# POWER.net
KiCad netlist of a schematic drawn in Altium Designer
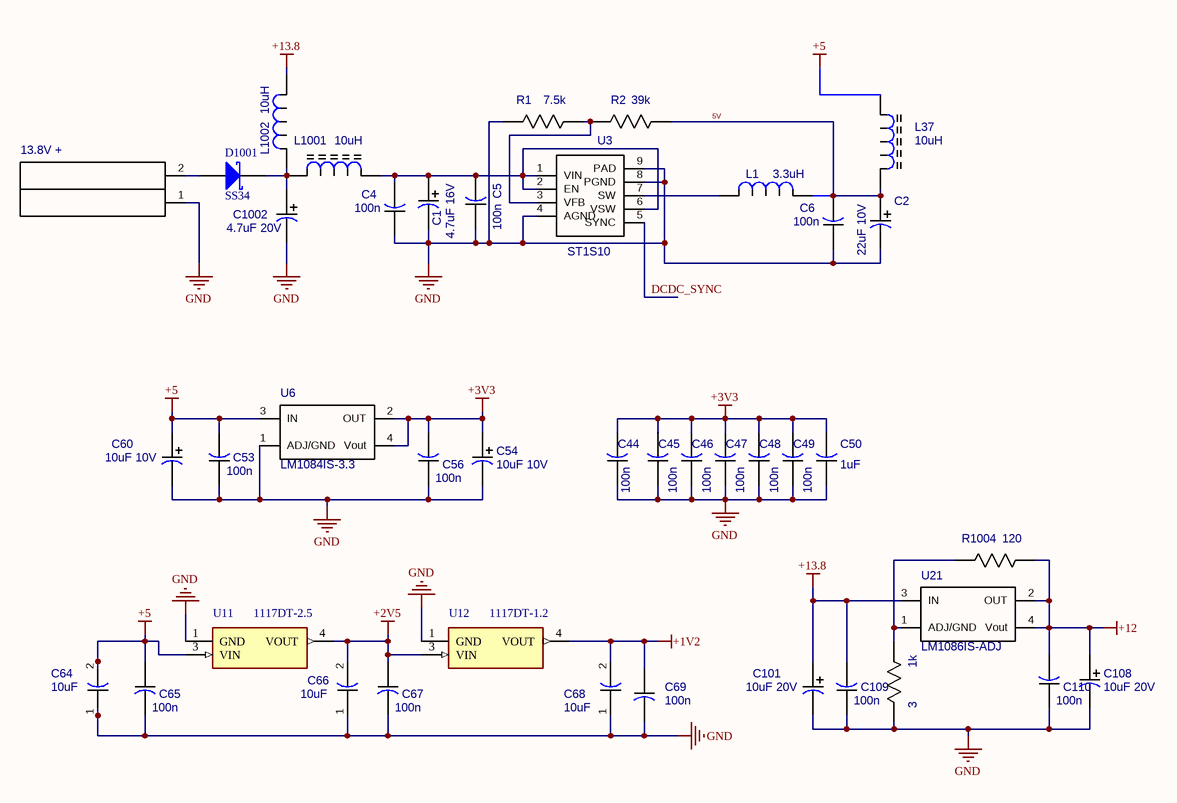
[diagram p0: POWER.SchDoc]

(export (version "E")
  (design (tool "Eeschema 10.0.6"))
  (components
    (comp (ref "3")
      (value "1k")
      (footprint "RES_0805")
      (description "RES_0805")
      (fields (field (name "Comment") "39k"))
      (libsource (lib "*") (part "RES_0805"))
    )
    (comp (ref "13.8V +") (value "JX2") (footprint "JX2") (libsource (lib "*") (part "JX2")))
    (comp (ref "C1")
      (value "4.7uF 16V")
      (footprint "SMC")
      (description "CAPAE_6.6x6.6h5.4")
      (libsource (lib "*") (part "CAPAE_6.6x6.6h5.4"))
    )
    (comp (ref "C2")
      (value "22uF 10V")
      (footprint "CAPAE_4.3x4.3h5.4")
      (description "CAPAE_4.3x4.3h5.4")
      (libsource (lib "*") (part "CAPAE_4.3x4.3h5.4"))
    )
    (comp (ref "C4")
      (value "100n")
      (footprint "CAP_0805")
      (description "CAP_0805")
      (libsource (lib "*") (part "CAP_0805"))
    )
    (comp (ref "C5")
      (value "100n")
      (footprint "CAP_0805")
      (description "CAP_0805")
      (libsource (lib "*") (part "CAP_0805"))
    )
    (comp (ref "C6")
      (value "100n")
      (footprint "CAP_0805")
      (description "CAP_0805")
      (libsource (lib "*") (part "CAP_0805"))
    )
    (comp (ref "C44")
      (value "100n")
      (footprint "CAP_0805")
      (description "CAP_0805")
      (libsource (lib "*") (part "CAP_0805"))
    )
    (comp (ref "C45")
      (value "100n")
      (footprint "CAP_0805")
      (description "CAP_0805")
      (libsource (lib "*") (part "CAP_0805"))
    )
    (comp (ref "C46")
      (value "100n")
      (footprint "CAP_0805")
      (description "CAP_0805")
      (libsource (lib "*") (part "CAP_0805"))
    )
    (comp (ref "C47")
      (value "100n")
      (footprint "CAP_0805")
      (description "CAP_0805")
      (libsource (lib "*") (part "CAP_0805"))
    )
    (comp (ref "C48")
      (value "100n")
      (footprint "CAP_0805")
      (description "CAP_0805")
      (libsource (lib "*") (part "CAP_0805"))
    )
    (comp (ref "C49")
      (value "100n")
      (footprint "CAP_0805")
      (description "CAP_0805")
      (libsource (lib "*") (part "CAP_0805"))
    )
    (comp (ref "C50")
      (value "1uF")
      (footprint "CAP_0805")
      (description "CAP_0805")
      (fields (field (name "Comment") "10uF"))
      (libsource (lib "*") (part "CAP_0805"))
    )
    (comp (ref "C53")
      (value "100n")
      (footprint "CAP_0805")
      (description "CAP_0805")
      (libsource (lib "*") (part "CAP_0805"))
    )
    (comp (ref "C54")
      (value "10uF 10V")
      (footprint "CAPAE_4.3x4.3h5.4")
      (description "CAPAE_4.3x4.3h5.4")
      (libsource (lib "*") (part "CAPAE_4.3x4.3h5.4"))
    )
    (comp (ref "C56")
      (value "100n")
      (footprint "CAP_0805")
      (description "CAP_0805")
      (libsource (lib "*") (part "CAP_0805"))
    )
    (comp (ref "C60")
      (value "10uF 10V")
      (footprint "CAPAE_4.3x4.3h5.4")
      (description "CAPAE_4.3x4.3h5.4")
      (libsource (lib "*") (part "CAPAE_4.3x4.3h5.4"))
    )
    (comp (ref "C64")
      (value "10uF")
      (footprint "CAP_0805")
      (description "CAP_0805")
      (libsource (lib "MOTHERBOARD") (part "CAP_0805"))
    )
    (comp (ref "C65")
      (value "100n")
      (footprint "CAP_0805")
      (description "CAP_0805")
      (libsource (lib "*") (part "CAP_0805"))
    )
    (comp (ref "C66")
      (value "10uF")
      (footprint "CAP_0805")
      (description "CAP_0805")
      (libsource (lib "MOTHERBOARD") (part "CAP_0805"))
    )
    (comp (ref "C67")
      (value "100n")
      (footprint "CAP_0805")
      (description "CAP_0805")
      (libsource (lib "*") (part "CAP_0805"))
    )
    (comp (ref "C68")
      (value "10uF")
      (footprint "CAP_0805")
      (description "CAP_0805")
      (libsource (lib "MOTHERBOARD") (part "CAP_0805"))
    )
    (comp (ref "C69")
      (value "100n")
      (footprint "CAP_0805")
      (description "CAP_0805")
      (libsource (lib "*") (part "CAP_0805"))
    )
    (comp (ref "C101")
      (value "10uF 20V")
      (footprint "CAPAE_4.3x4.3h5.4")
      (description "CAPAE_4.3x4.3h5.4")
      (libsource (lib "*") (part "CAPAE_4.3x4.3h5.4"))
    )
    (comp (ref "C108")
      (value "10uF 20V")
      (footprint "CAPAE_4.3x4.3h5.4")
      (description "CAPAE_4.3x4.3h5.4")
      (libsource (lib "*") (part "CAPAE_4.3x4.3h5.4"))
    )
    (comp (ref "C109")
      (value "100n")
      (footprint "CAP_0805")
      (description "CAP_0805")
      (libsource (lib "*") (part "CAP_0805"))
    )
    (comp (ref "C110")
      (value "100n")
      (footprint "CAP_0805")
      (description "CAP_0805")
      (libsource (lib "*") (part "CAP_0805"))
    )
    (comp (ref "C1002")
      (value "4.7uF 20V")
      (footprint "CAPAE_4.3x4.3h5.4")
      (description "CAPAE_4.3x4.3h5.4")
      (fields (field (name "Comment") "10uF 10V"))
      (libsource (lib "*") (part "CAPAE_4.3x4.3h5.4"))
    )
    (comp (ref "D1001")
      (value "SS34")
      (footprint "SMB")
      (description "Schottky Diode")
      (fields (field (name "PUBLISHER") "Altium Limited"))
      (libsource (lib "Miscellaneous Devices") (part "D Schottky"))
    )
    (comp (ref "L1")
      (value "3.3uH")
      (footprint "IND_1812")
      (description "IND_1812")
      (libsource (lib "*") (part "IND_1812"))
    )
    (comp (ref "L37")
      (value "10uH")
      (footprint "IND_7x7")
      (description "Inductor")
      (libsource (lib "MOTHERBOARD_1") (part "IND_FERRITE_CORE"))
    )
    (comp (ref "L1001")
      (value "10uH")
      (footprint "IND_7x7")
      (description "Inductor")
      (libsource (lib "MOTHERBOARD_1") (part "IND_FERRITE_CORE"))
    )
    (comp (ref "L1002")
      (value "10uH")
      (footprint "IND_1812")
      (description "IND_1812")
      (libsource (lib "*") (part "IND_1812"))
    )
    (comp (ref "R1")
      (value "7.5k")
      (footprint "RES_0805")
      (description "RES_0805")
      (libsource (lib "*") (part "RES_0805"))
    )
    (comp (ref "R2")
      (value "39k")
      (footprint "RES_0805")
      (description "RES_0805")
      (libsource (lib "*") (part "RES_0805"))
    )
    (comp (ref "R1004")
      (value "120")
      (footprint "RES_0805")
      (description "RES_0805")
      (libsource (lib "*") (part "RES_0805"))
    )
    (comp (ref "U3") (value "ST1S10") (footprint "ST1S10") (libsource (lib "*") (part "ST1S10")))
    (comp (ref "U6")
      (value "LM1084IS-3.3")
      (footprint "LM1085-3.3")
      (libsource (lib "*") (part "LM1085-3.3"))
    )
    (comp (ref "U11")
      (value "1117DT-2.5")
      (footprint "SamacSys:TO228P991X238-3N")
      (description "LD1117DT-2.5 DPAK")
      (fields
        (field (name "MANUFACTURER_PART_NUMBER") "LM1117DT-ADJ")
        (field (name "MOUSER PART NUMBER") "926-LM1117DT-ADJ")
      )
      (libsource (lib "*") (part "LM1117DT-ADJ"))
    )
    (comp (ref "U12")
      (value "1117DT-1.2")
      (footprint "SamacSys:TO228P991X238-3N")
      (description "LD1117DT-1.2 DPAK")
      (fields
        (field (name "MANUFACTURER_PART_NUMBER") "LM1117DT-ADJ")
        (field (name "MOUSER PART NUMBER") "926-LM1117DT-ADJ")
      )
      (libsource (lib "*") (part "LM1117DT-ADJ"))
    )
    (comp (ref "U21")
      (value "LM1086IS-ADJ")
      (footprint "LM1085-3.3")
      (description "LM1084IS-3.3")
      (libsource (lib "*") (part "LM1085-3.3"))
    )
  )
  (nets
    (net (code "1") (name "+1V2") (class "Default")
      (node (ref "C68") (pin "2") (pinfunction "2_2") (pintype "passive"))
      (node (ref "C69") (pin "1") (pinfunction "1_1") (pintype "passive"))
      (node (ref "U12") (pin "4") (pinfunction "VOUT_4") (pintype "output"))
    )
    (net (code "2") (name "+2V5") (class "Default")
      (node (ref "C66") (pin "2") (pinfunction "2_2") (pintype "passive"))
      (node (ref "C67") (pin "1") (pinfunction "1_1") (pintype "passive"))
      (node (ref "U11") (pin "4") (pinfunction "VOUT_4") (pintype "output"))
      (node (ref "U12") (pin "3") (pinfunction "VIN_3") (pintype "input"))
    )
    (net (code "3") (name "+3V3") (class "Default")
      (node (ref "C44") (pin "2") (pinfunction "2_2") (pintype "passive"))
      (node (ref "C45") (pin "2") (pinfunction "2_2") (pintype "passive"))
      (node (ref "C46") (pin "2") (pinfunction "2_2") (pintype "passive"))
      (node (ref "C47") (pin "2") (pinfunction "2_2") (pintype "passive"))
      (node (ref "C48") (pin "2") (pinfunction "2_2") (pintype "passive"))
      (node (ref "C49") (pin "2") (pinfunction "2_2") (pintype "passive"))
      (node (ref "C50") (pin "2") (pinfunction "2_2") (pintype "passive"))
      (node (ref "C54") (pin "1") (pinfunction "PLUS_1") (pintype "passive"))
      (node (ref "C56") (pin "2") (pinfunction "2_2") (pintype "passive"))
      (node (ref "U6") (pin "2") (pinfunction "OUT_2") (pintype "passive"))
      (node (ref "U6") (pin "4") (pinfunction "Vout_4") (pintype "passive"))
    )
    (net (code "4") (name "+5") (class "Default")
      (node (ref "C53") (pin "2") (pinfunction "2_2") (pintype "passive"))
      (node (ref "C60") (pin "1") (pinfunction "PLUS_1") (pintype "passive"))
      (node (ref "C64") (pin "2") (pinfunction "2_2") (pintype "passive"))
      (node (ref "C65") (pin "1") (pinfunction "1_1") (pintype "passive"))
      (node (ref "L37") (pin "1") (pinfunction "A_1") (pintype "passive"))
      (node (ref "U11") (pin "3") (pinfunction "VIN_3") (pintype "input"))
      (node (ref "U6") (pin "3") (pinfunction "IN_3") (pintype "passive"))
    )
    (net (code "5") (name "+12") (class "Default")
      (node (ref "C108") (pin "1") (pinfunction "PLUS_1") (pintype "passive"))
      (node (ref "C110") (pin "2") (pinfunction "2_2") (pintype "passive"))
      (node (ref "R1004") (pin "2") (pinfunction "2_2") (pintype "passive"))
      (node (ref "U21") (pin "2") (pinfunction "OUT_2") (pintype "passive"))
      (node (ref "U21") (pin "4") (pinfunction "Vout_4") (pintype "passive"))
    )
    (net (code "6") (name "+13.8") (class "Default")
      (node (ref "C101") (pin "1") (pinfunction "PLUS_1") (pintype "passive"))
      (node (ref "C109") (pin "2") (pinfunction "2_2") (pintype "passive"))
      (node (ref "L1002") (pin "2") (pinfunction "2_2") (pintype "passive"))
      (node (ref "U21") (pin "3") (pinfunction "IN_3") (pintype "passive"))
    )
    (net (code "7") (name "/5V") (class "Default")
      (node (ref "C2") (pin "1") (pinfunction "PLUS_1") (pintype "passive"))
      (node (ref "C6") (pin "2") (pinfunction "2_2") (pintype "passive"))
      (node (ref "L1") (pin "2") (pinfunction "2_2") (pintype "passive"))
      (node (ref "L37") (pin "2") (pinfunction "B_2") (pintype "passive"))
      (node (ref "R2") (pin "2") (pinfunction "2_2") (pintype "passive"))
    )
    (net (code "8") (name "/DCDC_SYNC") (class "Default")
      (node (ref "U3") (pin "5") (pinfunction "SYNC_5") (pintype "passive"))
    )
    (net (code "9") (name "GND") (class "Default")
      (node (ref "13.8V +") (pin "1") (pinfunction "2_1") (pintype "passive"))
      (node (ref "3") (pin "1") (pinfunction "1_1") (pintype "passive"))
      (node (ref "C1") (pin "2") (pinfunction "MINUS_2") (pintype "passive"))
      (node (ref "C1002") (pin "2") (pinfunction "MINUS_2") (pintype "passive"))
      (node (ref "C101") (pin "2") (pinfunction "MINUS_2") (pintype "passive"))
      (node (ref "C108") (pin "2") (pinfunction "MINUS_2") (pintype "passive"))
      (node (ref "C109") (pin "1") (pinfunction "1_1") (pintype "passive"))
      (node (ref "C110") (pin "1") (pinfunction "1_1") (pintype "passive"))
      (node (ref "C2") (pin "2") (pinfunction "MINUS_2") (pintype "passive"))
      (node (ref "C4") (pin "1") (pinfunction "1_1") (pintype "passive"))
      (node (ref "C44") (pin "1") (pinfunction "1_1") (pintype "passive"))
      (node (ref "C45") (pin "1") (pinfunction "1_1") (pintype "passive"))
      (node (ref "C46") (pin "1") (pinfunction "1_1") (pintype "passive"))
      (node (ref "C47") (pin "1") (pinfunction "1_1") (pintype "passive"))
      (node (ref "C48") (pin "1") (pinfunction "1_1") (pintype "passive"))
      (node (ref "C49") (pin "1") (pinfunction "1_1") (pintype "passive"))
      (node (ref "C5") (pin "1") (pinfunction "1_1") (pintype "passive"))
      (node (ref "C50") (pin "1") (pinfunction "1_1") (pintype "passive"))
      (node (ref "C53") (pin "1") (pinfunction "1_1") (pintype "passive"))
      (node (ref "C54") (pin "2") (pinfunction "MINUS_2") (pintype "passive"))
      (node (ref "C56") (pin "1") (pinfunction "1_1") (pintype "passive"))
      (node (ref "C6") (pin "1") (pinfunction "1_1") (pintype "passive"))
      (node (ref "C60") (pin "2") (pinfunction "MINUS_2") (pintype "passive"))
      (node (ref "C64") (pin "1") (pinfunction "1_1") (pintype "passive"))
      (node (ref "C65") (pin "2") (pinfunction "2_2") (pintype "passive"))
      (node (ref "C66") (pin "1") (pinfunction "1_1") (pintype "passive"))
      (node (ref "C67") (pin "2") (pinfunction "2_2") (pintype "passive"))
      (node (ref "C68") (pin "1") (pinfunction "1_1") (pintype "passive"))
      (node (ref "C69") (pin "2") (pinfunction "2_2") (pintype "passive"))
      (node (ref "R1") (pin "1") (pinfunction "1_1") (pintype "passive"))
      (node (ref "U11") (pin "1") (pinfunction "GND_1") (pintype "passive"))
      (node (ref "U12") (pin "1") (pinfunction "GND_1") (pintype "passive"))
      (node (ref "U3") (pin "4") (pinfunction "AGND_4") (pintype "passive"))
      (node (ref "U3") (pin "8") (pinfunction "PGND_8") (pintype "passive"))
      (node (ref "U3") (pin "9") (pinfunction "PAD_9") (pintype "passive"))
      (node (ref "U6") (pin "1") (pinfunction "ADJ/GND_1") (pintype "passive"))
    )
    (net (code "10") (name "Net-(13.8V +-1)") (class "Default")
      (node (ref "13.8V +") (pin "2") (pinfunction "1_2") (pintype "passive"))
      (node (ref "D1001") (pin "1") (pinfunction "A_1") (pintype "passive"))
    )
    (net (code "11") (name "Net-(C1-PLUS)") (class "Default")
      (node (ref "C1") (pin "1") (pinfunction "PLUS_1") (pintype "passive"))
      (node (ref "C4") (pin "2") (pinfunction "2_2") (pintype "passive"))
      (node (ref "C5") (pin "2") (pinfunction "2_2") (pintype "passive"))
      (node (ref "L1001") (pin "2") (pinfunction "B_2") (pintype "passive"))
      (node (ref "U3") (pin "1") (pinfunction "VIN_1") (pintype "passive"))
      (node (ref "U3") (pin "2") (pinfunction "EN_2") (pintype "passive"))
      (node (ref "U3") (pin "6") (pinfunction "VSW_6") (pintype "passive"))
    )
    (net (code "12") (name "Net-(C1002-PLUS)") (class "Default")
      (node (ref "C1002") (pin "1") (pinfunction "PLUS_1") (pintype "passive"))
      (node (ref "D1001") (pin "2") (pinfunction "K_2") (pintype "passive"))
      (node (ref "L1001") (pin "1") (pinfunction "A_1") (pintype "passive"))
      (node (ref "L1002") (pin "1") (pinfunction "1_1") (pintype "passive"))
    )
    (net (code "13") (name "Net-(U3-SW)") (class "Default")
      (node (ref "L1") (pin "1") (pinfunction "1_1") (pintype "passive"))
      (node (ref "U3") (pin "7") (pinfunction "SW_7") (pintype "passive"))
    )
    (net (code "14") (name "Net-(U3-VFB)") (class "Default")
      (node (ref "R1") (pin "2") (pinfunction "2_2") (pintype "passive"))
      (node (ref "R2") (pin "1") (pinfunction "1_1") (pintype "passive"))
      (node (ref "U3") (pin "3") (pinfunction "VFB_3") (pintype "passive"))
    )
    (net (code "15") (name "Net-(U21-ADJ{slash}GND)") (class "Default")
      (node (ref "3") (pin "2") (pinfunction "2_2") (pintype "passive"))
      (node (ref "R1004") (pin "1") (pinfunction "1_1") (pintype "passive"))
      (node (ref "U21") (pin "1") (pinfunction "ADJ/GND_1") (pintype "passive"))
    )
  )
)
